# power2pix_leakmodule_v2.net
KiCad netlist of a schematic drawn in Altium Designer
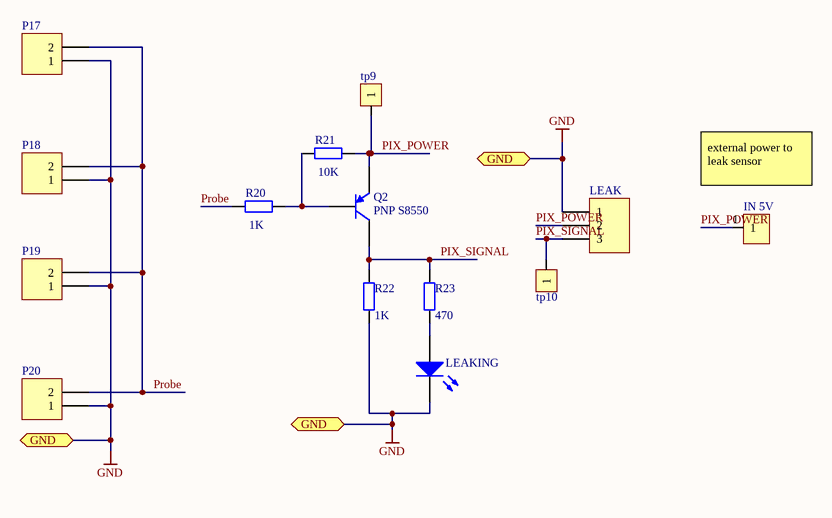
[diagram p0: power2pix_leakmodule_v2.SchDoc]

(export (version "E")
  (design (tool "Eeschema 10.0.6"))
  (components
    (comp (ref "IN 5V")
      (value "connector1")
      (footprint "connector1")
      (libsource (lib "power2pix_sch_lib") (part "connector1"))
    )
    (comp (ref "LEAK")
      (value "Header 3")
      (footprint "HDR1X3")
      (description "Header, 3-Pin")
      (fields (field (name "PUBLISHER") "Altium Limited"))
      (libsource (lib "Miscellaneous Connectors") (part "Header 3"))
    )
    (comp (ref "LEAKING")
      (value "LED0")
      (footprint "6-0805_L")
      (description "Typical INFRARED GaAs LED")
      (fields (field (name "PUBLISHER") "Altium Limited"))
      (libsource (lib "Miscellaneous Devices") (part "LED0"))
    )
    (comp (ref "P17")
      (value "Header 2")
      (footprint "headerX2")
      (description "Header, 2-Pin")
      (fields (field (name "PUBLISHER") "Altium Limited"))
      (libsource (lib "Miscellaneous Connectors") (part "Header 2"))
    )
    (comp (ref "P18")
      (value "Header 2")
      (footprint "headerX2")
      (description "Header, 2-Pin")
      (fields (field (name "PUBLISHER") "Altium Limited"))
      (libsource (lib "Miscellaneous Connectors") (part "Header 2"))
    )
    (comp (ref "P19")
      (value "Header 2")
      (footprint "headerX2")
      (description "Header, 2-Pin")
      (fields (field (name "PUBLISHER") "Altium Limited"))
      (libsource (lib "Miscellaneous Connectors") (part "Header 2"))
    )
    (comp (ref "P20")
      (value "Header 2")
      (footprint "headerX2")
      (description "Header, 2-Pin")
      (fields (field (name "PUBLISHER") "Altium Limited"))
      (libsource (lib "Miscellaneous Connectors") (part "Header 2"))
    )
    (comp (ref "Q2")
      (value "PNP S8550")
      (footprint "SOT89L")
      (description "PNP Bipolar Transistor")
      (fields (field (name "PUBLISHER") "Altium Limited"))
      (libsource (lib "Miscellaneous Devices") (part "PNP"))
    )
    (comp (ref "R20")
      (value "1K")
      (footprint "6-0805_L")
      (description "Resistor")
      (fields (field (name "Comment") "Res2") (field (name "PUBLISHER") "Altium Limited"))
      (libsource (lib "Miscellaneous Devices") (part "Res2"))
    )
    (comp (ref "R21")
      (value "10K")
      (footprint "6-0805_L")
      (description "Resistor")
      (fields (field (name "Comment") "Res2") (field (name "PUBLISHER") "Altium Limited"))
      (libsource (lib "Miscellaneous Devices") (part "Res2"))
    )
    (comp (ref "R22")
      (value "1K")
      (footprint "6-0805_L")
      (description "Resistor")
      (fields (field (name "Comment") "Res2") (field (name "PUBLISHER") "Altium Limited"))
      (libsource (lib "") (part "Res2_2"))
    )
    (comp (ref "R23")
      (value "470")
      (footprint "6-0805_L")
      (description "Resistor")
      (fields (field (name "Comment") "Res2") (field (name "PUBLISHER") "Altium Limited"))
      (libsource (lib "") (part "Res2_1"))
    )
    (comp (ref "tp9") (value "tp") (footprint "TestPoint") (libsource (lib "") (part "tp_1")))
    (comp (ref "tp10") (value "tp") (footprint "TestPoint") (libsource (lib "power2pix_sch_lib") (part "tp")))
  )
  (nets
    (net (code "1") (name "/PIX_POWER") (class "Default")
      (node (ref "IN 5V") (pin "1") (pinfunction "1_1") (pintype "passive"))
      (node (ref "LEAK") (pin "2") (pinfunction "2_2") (pintype "passive"))
      (node (ref "Q2") (pin "3") (pinfunction "E_3") (pintype "passive"))
      (node (ref "R21") (pin "1") (pinfunction "1_1") (pintype "passive"))
      (node (ref "tp9") (pin "1") (pinfunction "1_1") (pintype "passive"))
    )
    (net (code "2") (name "/PIX_SIGNAL") (class "Default")
      (node (ref "LEAK") (pin "3") (pinfunction "3_3") (pintype "passive"))
      (node (ref "Q2") (pin "2") (pinfunction "C_2") (pintype "passive"))
      (node (ref "R22") (pin "1") (pinfunction "1_1") (pintype "passive"))
      (node (ref "R23") (pin "2") (pinfunction "2_2") (pintype "passive"))
      (node (ref "tp10") (pin "1") (pinfunction "1_1") (pintype "passive"))
    )
    (net (code "3") (name "/Probe") (class "Default")
      (node (ref "P17") (pin "2") (pinfunction "2_2") (pintype "passive"))
      (node (ref "P18") (pin "2") (pinfunction "2_2") (pintype "passive"))
      (node (ref "P19") (pin "2") (pinfunction "2_2") (pintype "passive"))
      (node (ref "P20") (pin "2") (pinfunction "2_2") (pintype "passive"))
      (node (ref "R20") (pin "2") (pinfunction "2_2") (pintype "passive"))
    )
    (net (code "4") (name "GND") (class "Default")
      (node (ref "LEAK") (pin "1") (pinfunction "1_1") (pintype "passive"))
      (node (ref "LEAKING") (pin "2") (pinfunction "K_2") (pintype "passive"))
      (node (ref "P17") (pin "1") (pinfunction "1_1") (pintype "passive"))
      (node (ref "P18") (pin "1") (pinfunction "1_1") (pintype "passive"))
      (node (ref "P19") (pin "1") (pinfunction "1_1") (pintype "passive"))
      (node (ref "P20") (pin "1") (pinfunction "1_1") (pintype "passive"))
      (node (ref "R22") (pin "2") (pinfunction "2_2") (pintype "passive"))
    )
    (net (code "5") (name "Net-(LEAKING-A)") (class "Default")
      (node (ref "LEAKING") (pin "1") (pinfunction "A_1") (pintype "passive"))
      (node (ref "R23") (pin "1") (pinfunction "1_1") (pintype "passive"))
    )
    (net (code "6") (name "Net-(Q2-B)") (class "Default")
      (node (ref "Q2") (pin "1") (pinfunction "B_1") (pintype "passive"))
      (node (ref "R20") (pin "1") (pinfunction "1_1") (pintype "passive"))
      (node (ref "R21") (pin "2") (pinfunction "2_2") (pintype "passive"))
    )
  )
)
